# 4ButtonSwitch_Rev2_1.net
KiCad netlist of a schematic drawn in EAGLE
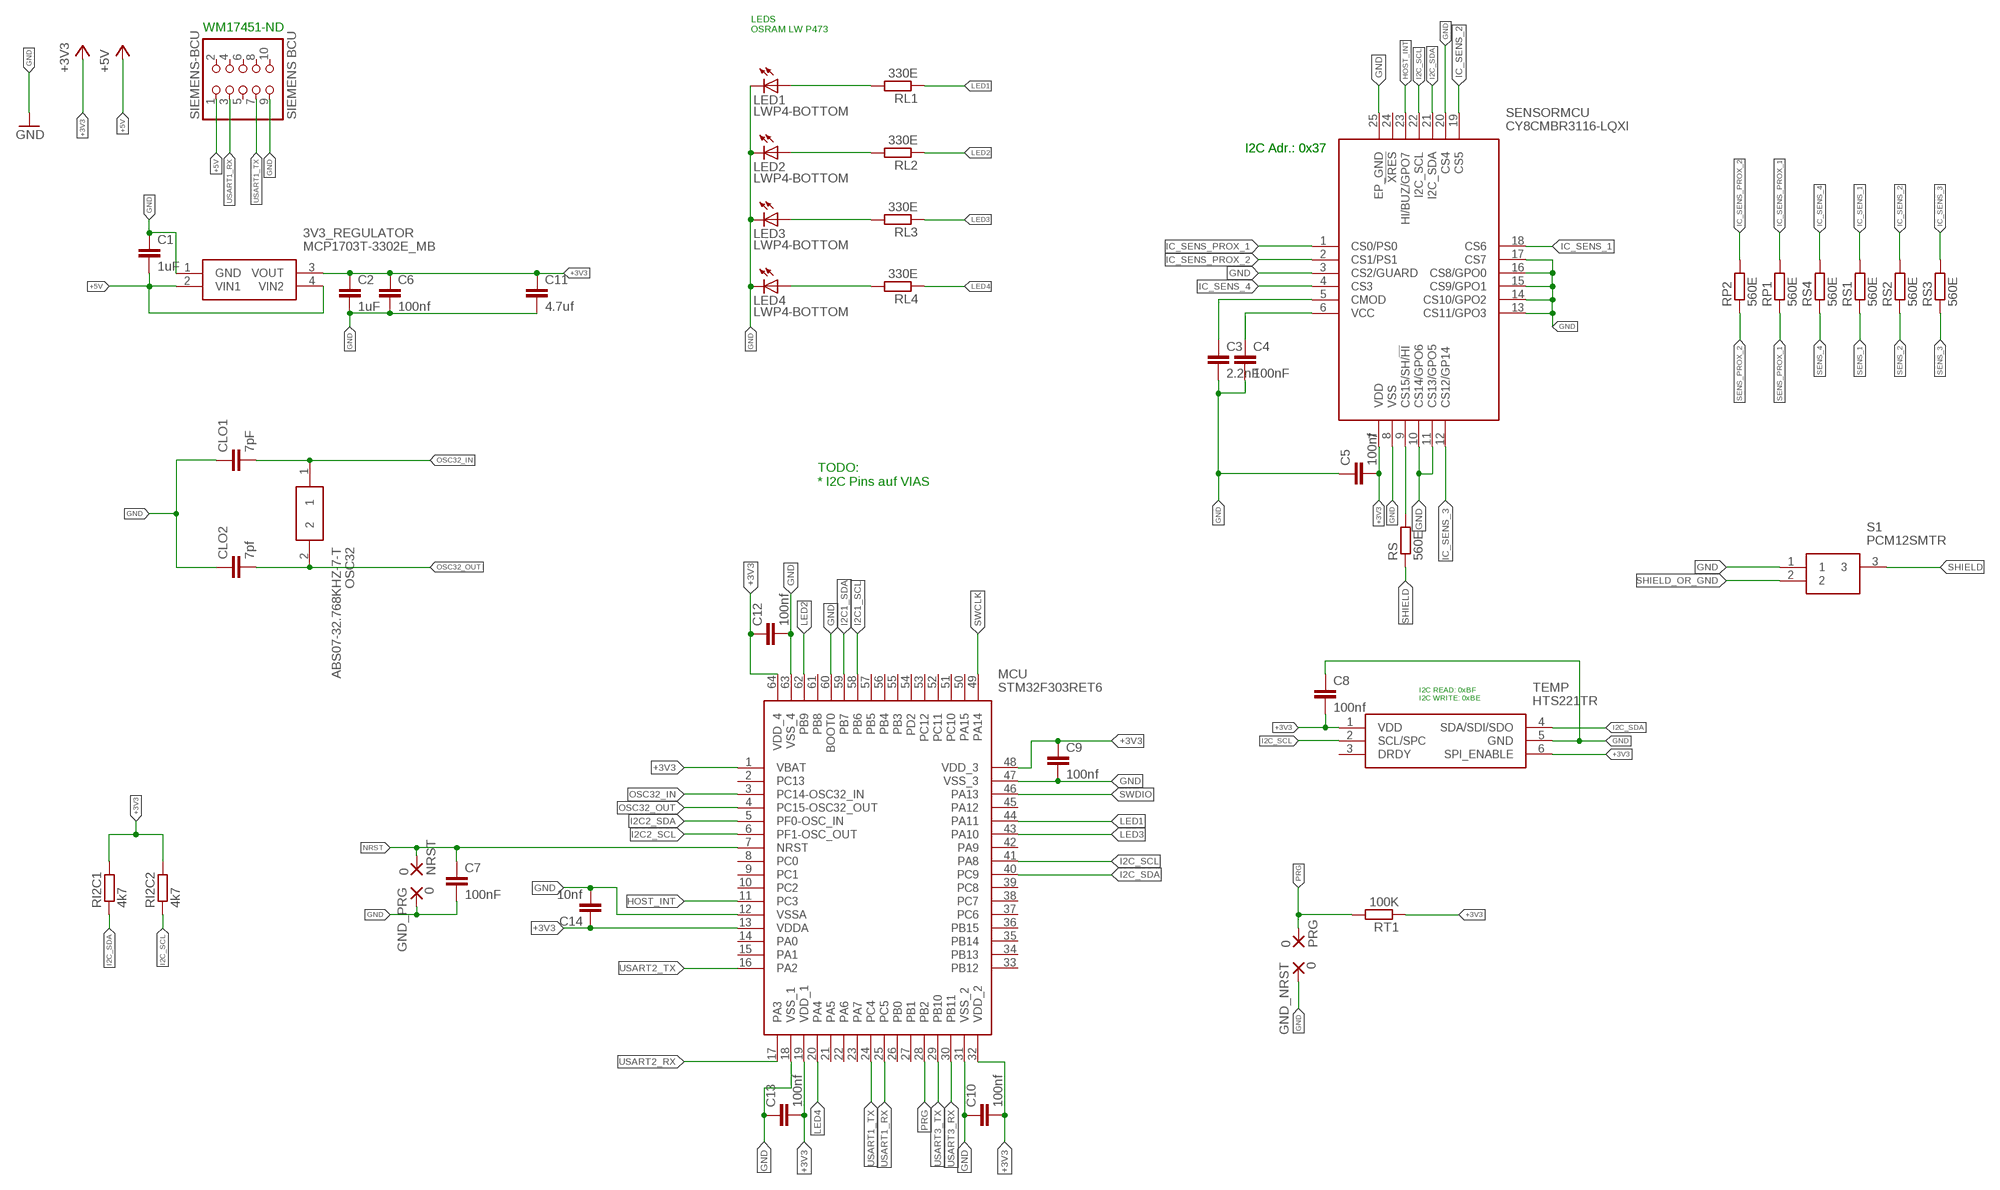
[diagram p0: schematic, sheet 1]

(export (version "E")
  (design (tool "Eeschema 10.0.6"))
  (components
    (comp (ref "3V3_REGULATOR")
      (value "MCP1703T-3302E_MB")
      (footprint "eagle-import:SOT-89(MB)")
      (fields
        (field (name "ARROW_PART_NUMBER") "MCP1703T-3302E/MB")
        (field (name "RS_PART_NUMBER") "9122916")
      )
      (libsource (lib "eagle-import") (part "MCP1703T-3302E_MB"))
    )
    (comp (ref "C1")
      (value "1uF")
      (footprint "eagle-import:C0402")
      (libsource (lib "eagle-import") (part "C-EUC0402"))
    )
    (comp (ref "C2")
      (value "1uF")
      (footprint "eagle-import:C0402")
      (libsource (lib "eagle-import") (part "C-EUC0402"))
    )
    (comp (ref "C3")
      (value "2.2nF")
      (footprint "eagle-import:C0402")
      (libsource (lib "eagle-import") (part "C-EUC0402"))
    )
    (comp (ref "C4")
      (value "100nF")
      (footprint "eagle-import:C0402")
      (libsource (lib "eagle-import") (part "C-EUC0402"))
    )
    (comp (ref "C5")
      (value "100nf")
      (footprint "eagle-import:C0402")
      (libsource (lib "eagle-import") (part "C-EUC0402"))
    )
    (comp (ref "C6")
      (value "100nf")
      (footprint "eagle-import:C0402")
      (libsource (lib "eagle-import") (part "C-EUC0402"))
    )
    (comp (ref "C7")
      (value "100nF")
      (footprint "eagle-import:C0402")
      (libsource (lib "eagle-import") (part "C-EUC0402"))
    )
    (comp (ref "C8")
      (value "100nf")
      (footprint "eagle-import:C0402")
      (libsource (lib "eagle-import") (part "C-EUC0402"))
    )
    (comp (ref "C9")
      (value "100nf")
      (footprint "eagle-import:C0402")
      (libsource (lib "eagle-import") (part "C-EUC0402"))
    )
    (comp (ref "C10")
      (value "100nf")
      (footprint "eagle-import:C0402")
      (libsource (lib "eagle-import") (part "C-EUC0402"))
    )
    (comp (ref "C11")
      (value "4.7uf")
      (footprint "eagle-import:C0402")
      (libsource (lib "eagle-import") (part "C-EUC0402"))
    )
    (comp (ref "C12")
      (value "100nf")
      (footprint "eagle-import:C0402")
      (libsource (lib "eagle-import") (part "C-EUC0402"))
    )
    (comp (ref "C13")
      (value "100nf")
      (footprint "eagle-import:C0402")
      (libsource (lib "eagle-import") (part "C-EUC0402"))
    )
    (comp (ref "C14")
      (value "10nf")
      (footprint "eagle-import:C0402")
      (libsource (lib "eagle-import") (part "C-EUC0402"))
    )
    (comp (ref "CLO1")
      (value "7pF")
      (footprint "eagle-import:C0402")
      (libsource (lib "eagle-import") (part "C-EUC0402"))
    )
    (comp (ref "CLO2")
      (value "7pf")
      (footprint "eagle-import:C0402")
      (libsource (lib "eagle-import") (part "C-EUC0402"))
    )
    (comp (ref "GND_NRST")
      (value "0")
      (footprint "eagle-import:SMD2,54-5,08")
      (libsource (lib "eagle-import") (part "SMD5"))
    )
    (comp (ref "GND_PRG")
      (value "0")
      (footprint "eagle-import:SMD2,54-5,08")
      (libsource (lib "eagle-import") (part "SMD5"))
    )
    (comp (ref "LED1")
      (value "LWP4-BOTTOM")
      (footprint "eagle-import:P47F-BOTTOM")
      (libsource (lib "eagle-import") (part "P4-BOTTOMLW"))
    )
    (comp (ref "LED2")
      (value "LWP4-BOTTOM")
      (footprint "eagle-import:P47F-BOTTOM")
      (libsource (lib "eagle-import") (part "P4-BOTTOMLW"))
    )
    (comp (ref "LED3")
      (value "LWP4-BOTTOM")
      (footprint "eagle-import:P47F-BOTTOM")
      (libsource (lib "eagle-import") (part "P4-BOTTOMLW"))
    )
    (comp (ref "LED4")
      (value "LWP4-BOTTOM")
      (footprint "eagle-import:P47F-BOTTOM")
      (libsource (lib "eagle-import") (part "P4-BOTTOMLW"))
    )
    (comp (ref "MCU")
      (value "STM32F303RET6")
      (footprint "eagle-import:QFP50P1200X1200X160-64N")
      (fields (field (name "RS_PART_NUMBER") "1458887"))
      (libsource (lib "eagle-import") (part "STM32F303RET6"))
    )
    (comp (ref "NRST")
      (value "0")
      (footprint "eagle-import:SMD2,54-5,08")
      (libsource (lib "eagle-import") (part "SMD5"))
    )
    (comp (ref "OSC32")
      (value "ABS07-32.768KHZ-7-T")
      (footprint "eagle-import:ABS-07")
      (fields (field (name "RS_PART_NUMBER") "1712773P"))
      (libsource (lib "eagle-import") (part "ABS07-32.768KHZ-7-T"))
    )
    (comp (ref "PRG")
      (value "0")
      (footprint "eagle-import:SMD2,54-5,08")
      (libsource (lib "eagle-import") (part "SMD5"))
    )
    (comp (ref "RI2C1")
      (value "4k7")
      (footprint "eagle-import:R0402")
      (libsource (lib "eagle-import") (part "R-EU_R0402"))
    )
    (comp (ref "RI2C2")
      (value "4k7")
      (footprint "eagle-import:R0402")
      (libsource (lib "eagle-import") (part "R-EU_R0402"))
    )
    (comp (ref "RL1")
      (value "330E")
      (footprint "eagle-import:R0402")
      (libsource (lib "eagle-import") (part "R-EU_R0402"))
    )
    (comp (ref "RL2")
      (value "330E")
      (footprint "eagle-import:R0402")
      (libsource (lib "eagle-import") (part "R-EU_R0402"))
    )
    (comp (ref "RL3")
      (value "330E")
      (footprint "eagle-import:R0402")
      (libsource (lib "eagle-import") (part "R-EU_R0402"))
    )
    (comp (ref "RL4")
      (value "330E")
      (footprint "eagle-import:R0402")
      (libsource (lib "eagle-import") (part "R-EU_R0402"))
    )
    (comp (ref "RP1")
      (value "560E")
      (footprint "eagle-import:R0402")
      (libsource (lib "eagle-import") (part "R-EU_R0402"))
    )
    (comp (ref "RP2")
      (value "560E")
      (footprint "eagle-import:R0402")
      (libsource (lib "eagle-import") (part "R-EU_R0402"))
    )
    (comp (ref "RS")
      (value "560E")
      (footprint "eagle-import:R0402")
      (libsource (lib "eagle-import") (part "R-EU_R0402"))
    )
    (comp (ref "RS1")
      (value "560E")
      (footprint "eagle-import:R0402")
      (libsource (lib "eagle-import") (part "R-EU_R0402"))
    )
    (comp (ref "RS2")
      (value "560E")
      (footprint "eagle-import:R0402")
      (libsource (lib "eagle-import") (part "R-EU_R0402"))
    )
    (comp (ref "RS3")
      (value "560E")
      (footprint "eagle-import:R0402")
      (libsource (lib "eagle-import") (part "R-EU_R0402"))
    )
    (comp (ref "RS4")
      (value "560E")
      (footprint "eagle-import:R0402")
      (libsource (lib "eagle-import") (part "R-EU_R0402"))
    )
    (comp (ref "RT1")
      (value "100K")
      (footprint "eagle-import:R0402")
      (libsource (lib "eagle-import") (part "R-EU_R0402"))
    )
    (comp (ref "S1")
      (value "PCM12SMTR")
      (footprint "eagle-import:PCM12SMTR_1")
      (fields (field (name "RS_PART_NUMBER") "7931721P"))
      (libsource (lib "eagle-import") (part "PCM12SMTR"))
    )
    (comp (ref "SENSORMCU")
      (value "CY8CMBR3116-LQXI")
      (footprint "eagle-import:QFN50P400X400X60-25N")
      (fields (field (name "RS_PART_NUMBER") "1242976P"))
      (libsource (lib "eagle-import") (part "CY8CMBR3116-LQXI"))
    )
    (comp (ref "SIEMENS-BCU")
      (value "SIEMENS BCU")
      (footprint "eagle-import:2X05SMD")
      (libsource (lib "eagle-import") (part "PINHD-2X5_2.54-SMD"))
    )
    (comp (ref "TEMP")
      (value "HTS221TR")
      (footprint "eagle-import:HLGA-6L")
      (fields (field (name "RS_PART_NUMBER") "1660935"))
      (libsource (lib "eagle-import") (part "HTS221TR"))
    )
  )
  (nets
    (net (code "1") (name "+3V3") (class "Default")
      (node (ref "3V3_REGULATOR") (pin "3") (pinfunction "VOUT_3") (pintype "bidirectional"))
      (node (ref "C10") (pin "2") (pinfunction "2_2") (pintype "passive"))
      (node (ref "C11") (pin "1") (pinfunction "1_1") (pintype "passive"))
      (node (ref "C12") (pin "1") (pinfunction "1_1") (pintype "passive"))
      (node (ref "C13") (pin "2") (pinfunction "2_2") (pintype "passive"))
      (node (ref "C14") (pin "1") (pinfunction "1_1") (pintype "passive"))
      (node (ref "C2") (pin "1") (pinfunction "1_1") (pintype "passive"))
      (node (ref "C5") (pin "2") (pinfunction "2_2") (pintype "passive"))
      (node (ref "C6") (pin "1") (pinfunction "1_1") (pintype "passive"))
      (node (ref "C8") (pin "2") (pinfunction "2_2") (pintype "passive"))
      (node (ref "C9") (pin "1") (pinfunction "1_1") (pintype "passive"))
      (node (ref "MCU") (pin "1") (pinfunction "VBAT_1") (pintype "power_in"))
      (node (ref "MCU") (pin "13") (pinfunction "VDDA_13") (pintype "power_in"))
      (node (ref "MCU") (pin "19") (pinfunction "VDD_1_19") (pintype "power_in"))
      (node (ref "MCU") (pin "32") (pinfunction "VDD_2_32") (pintype "power_in"))
      (node (ref "MCU") (pin "48") (pinfunction "VDD_3_48") (pintype "power_in"))
      (node (ref "MCU") (pin "64") (pinfunction "VDD_4_64") (pintype "power_in"))
      (node (ref "RI2C1") (pin "2") (pinfunction "2_2") (pintype "passive"))
      (node (ref "RI2C2") (pin "2") (pinfunction "2_2") (pintype "passive"))
      (node (ref "RT1") (pin "1") (pinfunction "1_1") (pintype "passive"))
      (node (ref "SENSORMCU") (pin "7") (pinfunction "VDD_7") (pintype "power_in"))
      (node (ref "TEMP") (pin "1") (pinfunction "VDD_1") (pintype "bidirectional"))
      (node (ref "TEMP") (pin "6") (pinfunction "SPI_ENABLE_6") (pintype "bidirectional"))
    )
    (net (code "2") (name "+5V") (class "Default")
      (node (ref "3V3_REGULATOR") (pin "2") (pinfunction "VIN1_2") (pintype "bidirectional"))
      (node (ref "3V3_REGULATOR") (pin "4") (pinfunction "VIN2_4") (pintype "bidirectional"))
      (node (ref "C1") (pin "2") (pinfunction "2_2") (pintype "passive"))
      (node (ref "SIEMENS-BCU") (pin "1") (pinfunction "1_1") (pintype "passive"))
    )
    (net (code "3") (name "GND") (class "Default")
      (node (ref "3V3_REGULATOR") (pin "1") (pinfunction "GND_1") (pintype "bidirectional"))
      (node (ref "C1") (pin "1") (pinfunction "1_1") (pintype "passive"))
      (node (ref "C10") (pin "1") (pinfunction "1_1") (pintype "passive"))
      (node (ref "C11") (pin "2") (pinfunction "2_2") (pintype "passive"))
      (node (ref "C12") (pin "2") (pinfunction "2_2") (pintype "passive"))
      (node (ref "C13") (pin "1") (pinfunction "1_1") (pintype "passive"))
      (node (ref "C14") (pin "2") (pinfunction "2_2") (pintype "passive"))
      (node (ref "C2") (pin "2") (pinfunction "2_2") (pintype "passive"))
      (node (ref "C3") (pin "2") (pinfunction "2_2") (pintype "passive"))
      (node (ref "C4") (pin "2") (pinfunction "2_2") (pintype "passive"))
      (node (ref "C5") (pin "1") (pinfunction "1_1") (pintype "passive"))
      (node (ref "C6") (pin "2") (pinfunction "2_2") (pintype "passive"))
      (node (ref "C7") (pin "2") (pinfunction "2_2") (pintype "passive"))
      (node (ref "C8") (pin "1") (pinfunction "1_1") (pintype "passive"))
      (node (ref "C9") (pin "2") (pinfunction "2_2") (pintype "passive"))
      (node (ref "CLO1") (pin "1") (pinfunction "1_1") (pintype "passive"))
      (node (ref "CLO2") (pin "1") (pinfunction "1_1") (pintype "passive"))
      (node (ref "GND_NRST") (pin "1") (pinfunction "P_1") (pintype "passive"))
      (node (ref "GND_PRG") (pin "1") (pinfunction "P_1") (pintype "passive"))
      (node (ref "LED1") (pin "C") (pinfunction "C_C") (pintype "passive"))
      (node (ref "LED2") (pin "C") (pinfunction "C_C") (pintype "passive"))
      (node (ref "LED3") (pin "C") (pinfunction "C_C") (pintype "passive"))
      (node (ref "LED4") (pin "C") (pinfunction "C_C") (pintype "passive"))
      (node (ref "MCU") (pin "12") (pinfunction "VSSA_12") (pintype "power_in"))
      (node (ref "MCU") (pin "18") (pinfunction "VSS_1_18") (pintype "power_in"))
      (node (ref "MCU") (pin "31") (pinfunction "VSS_2_31") (pintype "power_in"))
      (node (ref "MCU") (pin "47") (pinfunction "VSS_3_47") (pintype "power_in"))
      (node (ref "MCU") (pin "60") (pinfunction "BOOT0_60") (pintype "bidirectional"))
      (node (ref "MCU") (pin "63") (pinfunction "VSS_4_63") (pintype "power_in"))
      (node (ref "S1") (pin "1") (pinfunction "1_1") (pintype "bidirectional"))
      (node (ref "SENSORMCU") (pin "10") (pinfunction "CS14/GPO6_10") (pintype "input"))
      (node (ref "SENSORMCU") (pin "11") (pinfunction "CS13/GPO5_11") (pintype "input"))
      (node (ref "SENSORMCU") (pin "13") (pinfunction "CS11/GPO3_13") (pintype "input"))
      (node (ref "SENSORMCU") (pin "14") (pinfunction "CS10/GPO2_14") (pintype "input"))
      (node (ref "SENSORMCU") (pin "15") (pinfunction "CS9/GPO1_15") (pintype "input"))
      (node (ref "SENSORMCU") (pin "16") (pinfunction "CS8/GPO0_16") (pintype "input"))
      (node (ref "SENSORMCU") (pin "17") (pinfunction "CS7_17") (pintype "input"))
      (node (ref "SENSORMCU") (pin "20") (pinfunction "CS4_20") (pintype "input"))
      (node (ref "SENSORMCU") (pin "25") (pinfunction "EP_GND_25") (pintype "power_in"))
      (node (ref "SENSORMCU") (pin "3") (pinfunction "CS2/GUARD_3") (pintype "input"))
      (node (ref "SENSORMCU") (pin "8") (pinfunction "VSS_8") (pintype "power_in"))
      (node (ref "SIEMENS-BCU") (pin "9") (pinfunction "9_9") (pintype "passive"))
      (node (ref "TEMP") (pin "5") (pinfunction "GND_5") (pintype "bidirectional"))
    )
    (net (code "4") (name "HOST_INT") (class "Default")
      (node (ref "MCU") (pin "11") (pinfunction "PC3_11") (pintype "bidirectional"))
      (node (ref "SENSORMCU") (pin "23") (pinfunction "HI/BUZ/GPO7_23") (pintype "bidirectional"))
    )
    (net (code "5") (name "I2C1_SCL") (class "Default")
      (node (ref "MCU") (pin "58") (pinfunction "PB6_58") (pintype "bidirectional"))
    )
    (net (code "6") (name "I2C1_SDA") (class "Default")
      (node (ref "MCU") (pin "59") (pinfunction "PB7_59") (pintype "bidirectional"))
    )
    (net (code "7") (name "I2C2_SCL") (class "Default")
      (node (ref "MCU") (pin "6") (pinfunction "PF1-OSC_OUT_6") (pintype "bidirectional"))
    )
    (net (code "8") (name "I2C2_SDA") (class "Default")
      (node (ref "MCU") (pin "5") (pinfunction "PF0-OSC_IN_5") (pintype "bidirectional"))
    )
    (net (code "9") (name "I2C_SCL") (class "Default")
      (node (ref "MCU") (pin "41") (pinfunction "PA8_41") (pintype "bidirectional"))
      (node (ref "RI2C2") (pin "1") (pinfunction "1_1") (pintype "passive"))
      (node (ref "SENSORMCU") (pin "22") (pinfunction "I2C_SCL_22") (pintype "bidirectional"))
      (node (ref "TEMP") (pin "2") (pinfunction "SCL/SPC_2") (pintype "bidirectional"))
    )
    (net (code "10") (name "I2C_SDA") (class "Default")
      (node (ref "MCU") (pin "40") (pinfunction "PC9_40") (pintype "bidirectional"))
      (node (ref "RI2C1") (pin "1") (pinfunction "1_1") (pintype "passive"))
      (node (ref "SENSORMCU") (pin "21") (pinfunction "I2C_SDA_21") (pintype "bidirectional"))
      (node (ref "TEMP") (pin "4") (pinfunction "SDA/SDI/SDO_4") (pintype "bidirectional"))
    )
    (net (code "11") (name "IC_SENS_1") (class "Default")
      (node (ref "RS1") (pin "2") (pinfunction "2_2") (pintype "passive"))
      (node (ref "SENSORMCU") (pin "18") (pinfunction "CS6_18") (pintype "input"))
    )
    (net (code "12") (name "IC_SENS_2") (class "Default")
      (node (ref "RS2") (pin "2") (pinfunction "2_2") (pintype "passive"))
      (node (ref "SENSORMCU") (pin "19") (pinfunction "CS5_19") (pintype "input"))
    )
    (net (code "13") (name "IC_SENS_3") (class "Default")
      (node (ref "RS3") (pin "2") (pinfunction "2_2") (pintype "passive"))
      (node (ref "SENSORMCU") (pin "12") (pinfunction "CS12/GP14_12") (pintype "input"))
    )
    (net (code "14") (name "IC_SENS_4") (class "Default")
      (node (ref "RS4") (pin "2") (pinfunction "2_2") (pintype "passive"))
      (node (ref "SENSORMCU") (pin "4") (pinfunction "CS3_4") (pintype "input"))
    )
    (net (code "15") (name "IC_SENS_PROX_1") (class "Default")
      (node (ref "RP1") (pin "2") (pinfunction "2_2") (pintype "passive"))
      (node (ref "SENSORMCU") (pin "1") (pinfunction "CS0/PS0_1") (pintype "input"))
    )
    (net (code "16") (name "IC_SENS_PROX_2") (class "Default")
      (node (ref "RP2") (pin "2") (pinfunction "2_2") (pintype "passive"))
      (node (ref "SENSORMCU") (pin "2") (pinfunction "CS1/PS1_2") (pintype "input"))
    )
    (net (code "17") (name "LED1") (class "Default")
      (node (ref "MCU") (pin "44") (pinfunction "PA11_44") (pintype "bidirectional"))
      (node (ref "RL1") (pin "1") (pinfunction "1_1") (pintype "passive"))
    )
    (net (code "18") (name "LED2") (class "Default")
      (node (ref "MCU") (pin "62") (pinfunction "PB9_62") (pintype "bidirectional"))
      (node (ref "RL2") (pin "1") (pinfunction "1_1") (pintype "passive"))
    )
    (net (code "19") (name "LED3") (class "Default")
      (node (ref "MCU") (pin "43") (pinfunction "PA10_43") (pintype "bidirectional"))
      (node (ref "RL3") (pin "1") (pinfunction "1_1") (pintype "passive"))
    )
    (net (code "20") (name "LED4") (class "Default")
      (node (ref "MCU") (pin "20") (pinfunction "PA4_20") (pintype "bidirectional"))
      (node (ref "RL4") (pin "1") (pinfunction "1_1") (pintype "passive"))
    )
    (net (code "21") (name "NRST") (class "Default")
      (node (ref "C7") (pin "1") (pinfunction "1_1") (pintype "passive"))
      (node (ref "MCU") (pin "7") (pinfunction "NRST_7") (pintype "bidirectional"))
      (node (ref "NRST") (pin "1") (pinfunction "P_1") (pintype "passive"))
    )
    (net (code "22") (name "Net-(LED1-PadA)") (class "Default")
      (node (ref "LED1") (pin "A") (pinfunction "A_A") (pintype "passive"))
      (node (ref "RL1") (pin "2") (pinfunction "2_2") (pintype "passive"))
    )
    (net (code "23") (name "Net-(LED2-PadA)") (class "Default")
      (node (ref "LED2") (pin "A") (pinfunction "A_A") (pintype "passive"))
      (node (ref "RL2") (pin "2") (pinfunction "2_2") (pintype "passive"))
    )
    (net (code "24") (name "Net-(LED3-PadA)") (class "Default")
      (node (ref "LED3") (pin "A") (pinfunction "A_A") (pintype "passive"))
      (node (ref "RL3") (pin "2") (pinfunction "2_2") (pintype "passive"))
    )
    (net (code "25") (name "Net-(LED4-PadA)") (class "Default")
      (node (ref "LED4") (pin "A") (pinfunction "A_A") (pintype "passive"))
      (node (ref "RL4") (pin "2") (pinfunction "2_2") (pintype "passive"))
    )
    (net (code "26") (name "Net-(SENSORMCU-CMOD)") (class "Default")
      (node (ref "C3") (pin "1") (pinfunction "1_1") (pintype "passive"))
      (node (ref "SENSORMCU") (pin "5") (pinfunction "CMOD_5") (pintype "bidirectional"))
    )
    (net (code "27") (name "Net-(SENSORMCU-CS15{slash}SH{slash}~{HI})") (class "Default")
      (node (ref "RS") (pin "2") (pinfunction "2_2") (pintype "passive"))
      (node (ref "SENSORMCU") (pin "9") (pinfunction "CS15/SH/~{HI}_9") (pintype "input"))
    )
    (net (code "28") (name "Net-(SENSORMCU-VCC)") (class "Default")
      (node (ref "C4") (pin "1") (pinfunction "1_1") (pintype "passive"))
      (node (ref "SENSORMCU") (pin "6") (pinfunction "VCC_6") (pintype "power_in"))
    )
    (net (code "29") (name "OSC32_IN") (class "Default")
      (node (ref "CLO1") (pin "2") (pinfunction "2_2") (pintype "passive"))
      (node (ref "MCU") (pin "3") (pinfunction "PC14-OSC32_IN_3") (pintype "bidirectional"))
      (node (ref "OSC32") (pin "1") (pinfunction "1_1") (pintype "bidirectional"))
    )
    (net (code "30") (name "OSC32_OUT") (class "Default")
      (node (ref "CLO2") (pin "2") (pinfunction "2_2") (pintype "passive"))
      (node (ref "MCU") (pin "4") (pinfunction "PC15-OSC32_OUT_4") (pintype "bidirectional"))
      (node (ref "OSC32") (pin "2") (pinfunction "2_2") (pintype "bidirectional"))
    )
    (net (code "31") (name "PRG") (class "Default")
      (node (ref "MCU") (pin "28") (pinfunction "PB2_28") (pintype "bidirectional"))
      (node (ref "PRG") (pin "1") (pinfunction "P_1") (pintype "passive"))
      (node (ref "RT1") (pin "2") (pinfunction "2_2") (pintype "passive"))
    )
    (net (code "32") (name "SENS_1") (class "Default")
      (node (ref "RS1") (pin "1") (pinfunction "1_1") (pintype "passive"))
    )
    (net (code "33") (name "SENS_2") (class "Default")
      (node (ref "RS2") (pin "1") (pinfunction "1_1") (pintype "passive"))
    )
    (net (code "34") (name "SENS_3") (class "Default")
      (node (ref "RS3") (pin "1") (pinfunction "1_1") (pintype "passive"))
    )
    (net (code "35") (name "SENS_4") (class "Default")
      (node (ref "RS4") (pin "1") (pinfunction "1_1") (pintype "passive"))
    )
    (net (code "36") (name "SENS_PROX_1") (class "Default")
      (node (ref "RP1") (pin "1") (pinfunction "1_1") (pintype "passive"))
    )
    (net (code "37") (name "SENS_PROX_2") (class "Default")
      (node (ref "RP2") (pin "1") (pinfunction "1_1") (pintype "passive"))
    )
    (net (code "38") (name "SHIELD") (class "Default")
      (node (ref "RS") (pin "1") (pinfunction "1_1") (pintype "passive"))
      (node (ref "S1") (pin "3") (pinfunction "3_3") (pintype "bidirectional"))
    )
    (net (code "39") (name "SHIELD_OR_GND") (class "Default")
      (node (ref "S1") (pin "2") (pinfunction "2_2") (pintype "bidirectional"))
    )
    (net (code "40") (name "SWCLK") (class "Default")
      (node (ref "MCU") (pin "49") (pinfunction "PA14_49") (pintype "bidirectional"))
    )
    (net (code "41") (name "SWDIO") (class "Default")
      (node (ref "MCU") (pin "46") (pinfunction "PA13_46") (pintype "bidirectional"))
    )
    (net (code "42") (name "USART1_RX") (class "Default")
      (node (ref "MCU") (pin "25") (pinfunction "PC5_25") (pintype "bidirectional"))
      (node (ref "SIEMENS-BCU") (pin "3") (pinfunction "3_3") (pintype "passive"))
    )
    (net (code "43") (name "USART1_TX") (class "Default")
      (node (ref "MCU") (pin "24") (pinfunction "PC4_24") (pintype "bidirectional"))
      (node (ref "SIEMENS-BCU") (pin "7") (pinfunction "7_7") (pintype "passive"))
    )
    (net (code "44") (name "USART2_RX") (class "Default")
      (node (ref "MCU") (pin "17") (pinfunction "PA3_17") (pintype "bidirectional"))
    )
    (net (code "45") (name "USART2_TX") (class "Default")
      (node (ref "MCU") (pin "16") (pinfunction "PA2_16") (pintype "bidirectional"))
    )
    (net (code "46") (name "USART3_RX") (class "Default")
      (node (ref "MCU") (pin "30") (pinfunction "PB11_30") (pintype "bidirectional"))
    )
    (net (code "47") (name "USART3_TX") (class "Default")
      (node (ref "MCU") (pin "29") (pinfunction "PB10_29") (pintype "bidirectional"))
    )
    (net (code "48") (name "unconnected-(MCU-PA0-Pad14)") (class "Default")
      (node (ref "MCU") (pin "14") (pinfunction "PA0_14") (pintype "bidirectional"))
    )
    (net (code "49") (name "unconnected-(MCU-PA1-Pad15)") (class "Default")
      (node (ref "MCU") (pin "15") (pinfunction "PA1_15") (pintype "bidirectional"))
    )
    (net (code "50") (name "unconnected-(MCU-PA5-Pad21)") (class "Default")
      (node (ref "MCU") (pin "21") (pinfunction "PA5_21") (pintype "bidirectional"))
    )
    (net (code "51") (name "unconnected-(MCU-PA6-Pad22)") (class "Default")
      (node (ref "MCU") (pin "22") (pinfunction "PA6_22") (pintype "bidirectional"))
    )
    (net (code "52") (name "unconnected-(MCU-PA7-Pad23)") (class "Default")
      (node (ref "MCU") (pin "23") (pinfunction "PA7_23") (pintype "bidirectional"))
    )
    (net (code "53") (name "unconnected-(MCU-PA9-Pad42)") (class "Default")
      (node (ref "MCU") (pin "42") (pinfunction "PA9_42") (pintype "bidirectional"))
    )
    (net (code "54") (name "unconnected-(MCU-PA12-Pad45)") (class "Default")
      (node (ref "MCU") (pin "45") (pinfunction "PA12_45") (pintype "bidirectional"))
    )
    (net (code "55") (name "unconnected-(MCU-PA15-Pad50)") (class "Default")
      (node (ref "MCU") (pin "50") (pinfunction "PA15_50") (pintype "bidirectional"))
    )
    (net (code "56") (name "unconnected-(MCU-PB0-Pad26)") (class "Default")
      (node (ref "MCU") (pin "26") (pinfunction "PB0_26") (pintype "bidirectional"))
    )
    (net (code "57") (name "unconnected-(MCU-PB1-Pad27)") (class "Default")
      (node (ref "MCU") (pin "27") (pinfunction "PB1_27") (pintype "bidirectional"))
    )
    (net (code "58") (name "unconnected-(MCU-PB3-Pad55)") (class "Default")
      (node (ref "MCU") (pin "55") (pinfunction "PB3_55") (pintype "bidirectional"))
    )
    (net (code "59") (name "unconnected-(MCU-PB4-Pad56)") (class "Default")
      (node (ref "MCU") (pin "56") (pinfunction "PB4_56") (pintype "bidirectional"))
    )
    (net (code "60") (name "unconnected-(MCU-PB5-Pad57)") (class "Default")
      (node (ref "MCU") (pin "57") (pinfunction "PB5_57") (pintype "bidirectional"))
    )
    (net (code "61") (name "unconnected-(MCU-PB8-Pad61)") (class "Default")
      (node (ref "MCU") (pin "61") (pinfunction "PB8_61") (pintype "bidirectional"))
    )
    (net (code "62") (name "unconnected-(MCU-PB12-Pad33)") (class "Default")
      (node (ref "MCU") (pin "33") (pinfunction "PB12_33") (pintype "bidirectional"))
    )
    (net (code "63") (name "unconnected-(MCU-PB13-Pad34)") (class "Default")
      (node (ref "MCU") (pin "34") (pinfunction "PB13_34") (pintype "bidirectional"))
    )
    (net (code "64") (name "unconnected-(MCU-PB14-Pad35)") (class "Default")
      (node (ref "MCU") (pin "35") (pinfunction "PB14_35") (pintype "bidirectional"))
    )
    (net (code "65") (name "unconnected-(MCU-PB15-Pad36)") (class "Default")
      (node (ref "MCU") (pin "36") (pinfunction "PB15_36") (pintype "bidirectional"))
    )
    (net (code "66") (name "unconnected-(MCU-PC0-Pad8)") (class "Default")
      (node (ref "MCU") (pin "8") (pinfunction "PC0_8") (pintype "bidirectional"))
    )
    (net (code "67") (name "unconnected-(MCU-PC1-Pad9)") (class "Default")
      (node (ref "MCU") (pin "9") (pinfunction "PC1_9") (pintype "bidirectional"))
    )
    (net (code "68") (name "unconnected-(MCU-PC2-Pad10)") (class "Default")
      (node (ref "MCU") (pin "10") (pinfunction "PC2_10") (pintype "bidirectional"))
    )
    (net (code "69") (name "unconnected-(MCU-PC6-Pad37)") (class "Default")
      (node (ref "MCU") (pin "37") (pinfunction "PC6_37") (pintype "bidirectional"))
    )
    (net (code "70") (name "unconnected-(MCU-PC7-Pad38)") (class "Default")
      (node (ref "MCU") (pin "38") (pinfunction "PC7_38") (pintype "bidirectional"))
    )
    (net (code "71") (name "unconnected-(MCU-PC8-Pad39)") (class "Default")
      (node (ref "MCU") (pin "39") (pinfunction "PC8_39") (pintype "bidirectional"))
    )
    (net (code "72") (name "unconnected-(MCU-PC10-Pad51)") (class "Default")
      (node (ref "MCU") (pin "51") (pinfunction "PC10_51") (pintype "bidirectional"))
    )
    (net (code "73") (name "unconnected-(MCU-PC11-Pad52)") (class "Default")
      (node (ref "MCU") (pin "52") (pinfunction "PC11_52") (pintype "bidirectional"))
    )
    (net (code "74") (name "unconnected-(MCU-PC12-Pad53)") (class "Default")
      (node (ref "MCU") (pin "53") (pinfunction "PC12_53") (pintype "bidirectional"))
    )
    (net (code "75") (name "unconnected-(MCU-PC13-Pad2)") (class "Default")
      (node (ref "MCU") (pin "2") (pinfunction "PC13_2") (pintype "bidirectional"))
    )
    (net (code "76") (name "unconnected-(MCU-PD2-Pad54)") (class "Default")
      (node (ref "MCU") (pin "54") (pinfunction "PD2_54") (pintype "bidirectional"))
    )
    (net (code "77") (name "unconnected-(SENSORMCU-~{XRES}-Pad24)") (class "Default")
      (node (ref "SENSORMCU") (pin "24") (pinfunction "~{XRES}_24") (pintype "bidirectional"))
    )
    (net (code "78") (name "unconnected-(SIEMENS-BCU-Pad2)") (class "Default")
      (node (ref "SIEMENS-BCU") (pin "2") (pinfunction "2_2") (pintype "passive"))
    )
    (net (code "79") (name "unconnected-(SIEMENS-BCU-Pad4)") (class "Default")
      (node (ref "SIEMENS-BCU") (pin "4") (pinfunction "4_4") (pintype "passive"))
    )
    (net (code "80") (name "unconnected-(SIEMENS-BCU-Pad5)") (class "Default")
      (node (ref "SIEMENS-BCU") (pin "5") (pinfunction "5_5") (pintype "passive"))
    )
    (net (code "81") (name "unconnected-(SIEMENS-BCU-Pad6)") (class "Default")
      (node (ref "SIEMENS-BCU") (pin "6") (pinfunction "6_6") (pintype "passive"))
    )
    (net (code "82") (name "unconnected-(SIEMENS-BCU-Pad8)") (class "Default")
      (node (ref "SIEMENS-BCU") (pin "8") (pinfunction "8_8") (pintype "passive"))
    )
    (net (code "83") (name "unconnected-(SIEMENS-BCU-Pad10)") (class "Default")
      (node (ref "SIEMENS-BCU") (pin "10") (pinfunction "10_10") (pintype "passive"))
    )
    (net (code "84") (name "unconnected-(TEMP-DRDY-Pad3)") (class "Default")
      (node (ref "TEMP") (pin "3") (pinfunction "DRDY_3") (pintype "bidirectional"))
    )
  )
)
